# ExtConn.net
KiCad netlist of a schematic drawn in Altium Designer
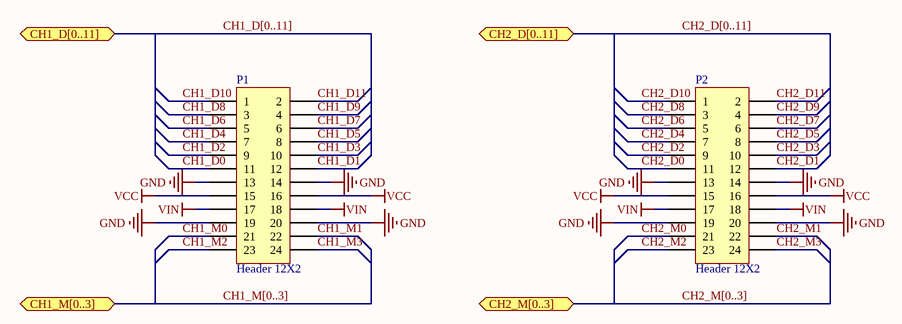
[diagram p0: ExtConn.SchDoc]

(export (version "E")
  (design (tool "Eeschema 10.0.6"))
  (components
    (comp (ref "P1")
      (value "Header 12X2")
      (footprint "HDR2X12")
      (description "Header, 12-Pin, Dual row")
      (fields (field (name "PUBLISHER") "Altium Limited"))
      (libsource (lib "Miscellaneous Connectors") (part "Header 12X2"))
    )
    (comp (ref "P2")
      (value "Header 12X2")
      (footprint "HDR2X12")
      (description "Header, 12-Pin, Dual row")
      (fields (field (name "PUBLISHER") "Altium Limited"))
      (libsource (lib "Miscellaneous Connectors") (part "Header 12X2"))
    )
  )
  (nets
    (net (code "1") (name "/CH1_D0") (class "Default")
      (node (ref "P1") (pin "11") (pinfunction "11_11") (pintype "passive"))
    )
    (net (code "2") (name "/CH1_D1") (class "Default")
      (node (ref "P1") (pin "12") (pinfunction "12_12") (pintype "passive"))
    )
    (net (code "3") (name "/CH1_D2") (class "Default")
      (node (ref "P1") (pin "9") (pinfunction "9_9") (pintype "passive"))
    )
    (net (code "4") (name "/CH1_D3") (class "Default")
      (node (ref "P1") (pin "10") (pinfunction "10_10") (pintype "passive"))
    )
    (net (code "5") (name "/CH1_D4") (class "Default")
      (node (ref "P1") (pin "7") (pinfunction "7_7") (pintype "passive"))
    )
    (net (code "6") (name "/CH1_D5") (class "Default")
      (node (ref "P1") (pin "8") (pinfunction "8_8") (pintype "passive"))
    )
    (net (code "7") (name "/CH1_D6") (class "Default")
      (node (ref "P1") (pin "5") (pinfunction "5_5") (pintype "passive"))
    )
    (net (code "8") (name "/CH1_D7") (class "Default")
      (node (ref "P1") (pin "6") (pinfunction "6_6") (pintype "passive"))
    )
    (net (code "9") (name "/CH1_D8") (class "Default")
      (node (ref "P1") (pin "3") (pinfunction "3_3") (pintype "passive"))
    )
    (net (code "10") (name "/CH1_D9") (class "Default")
      (node (ref "P1") (pin "4") (pinfunction "4_4") (pintype "passive"))
    )
    (net (code "11") (name "/CH1_D10") (class "Default")
      (node (ref "P1") (pin "1") (pinfunction "1_1") (pintype "passive"))
    )
    (net (code "12") (name "/CH1_D11") (class "Default")
      (node (ref "P1") (pin "2") (pinfunction "2_2") (pintype "passive"))
    )
    (net (code "14") (name "/CH1_M0") (class "Default")
      (node (ref "P1") (pin "21") (pinfunction "21_21") (pintype "passive"))
    )
    (net (code "15") (name "/CH1_M1") (class "Default")
      (node (ref "P1") (pin "22") (pinfunction "22_22") (pintype "passive"))
    )
    (net (code "16") (name "/CH1_M2") (class "Default")
      (node (ref "P1") (pin "23") (pinfunction "23_23") (pintype "passive"))
    )
    (net (code "17") (name "/CH1_M3") (class "Default")
      (node (ref "P1") (pin "24") (pinfunction "24_24") (pintype "passive"))
    )
    (net (code "19") (name "/CH2_D0") (class "Default")
      (node (ref "P2") (pin "11") (pinfunction "11_11") (pintype "passive"))
    )
    (net (code "20") (name "/CH2_D1") (class "Default")
      (node (ref "P2") (pin "12") (pinfunction "12_12") (pintype "passive"))
    )
    (net (code "21") (name "/CH2_D2") (class "Default")
      (node (ref "P2") (pin "9") (pinfunction "9_9") (pintype "passive"))
    )
    (net (code "22") (name "/CH2_D3") (class "Default")
      (node (ref "P2") (pin "10") (pinfunction "10_10") (pintype "passive"))
    )
    (net (code "23") (name "/CH2_D4") (class "Default")
      (node (ref "P2") (pin "7") (pinfunction "7_7") (pintype "passive"))
    )
    (net (code "24") (name "/CH2_D5") (class "Default")
      (node (ref "P2") (pin "8") (pinfunction "8_8") (pintype "passive"))
    )
    (net (code "25") (name "/CH2_D6") (class "Default")
      (node (ref "P2") (pin "5") (pinfunction "5_5") (pintype "passive"))
    )
    (net (code "26") (name "/CH2_D7") (class "Default")
      (node (ref "P2") (pin "6") (pinfunction "6_6") (pintype "passive"))
    )
    (net (code "27") (name "/CH2_D8") (class "Default")
      (node (ref "P2") (pin "3") (pinfunction "3_3") (pintype "passive"))
    )
    (net (code "28") (name "/CH2_D9") (class "Default")
      (node (ref "P2") (pin "4") (pinfunction "4_4") (pintype "passive"))
    )
    (net (code "29") (name "/CH2_D10") (class "Default")
      (node (ref "P2") (pin "1") (pinfunction "1_1") (pintype "passive"))
    )
    (net (code "30") (name "/CH2_D11") (class "Default")
      (node (ref "P2") (pin "2") (pinfunction "2_2") (pintype "passive"))
    )
    (net (code "32") (name "/CH2_M0") (class "Default")
      (node (ref "P2") (pin "21") (pinfunction "21_21") (pintype "passive"))
    )
    (net (code "33") (name "/CH2_M1") (class "Default")
      (node (ref "P2") (pin "22") (pinfunction "22_22") (pintype "passive"))
    )
    (net (code "34") (name "/CH2_M2") (class "Default")
      (node (ref "P2") (pin "23") (pinfunction "23_23") (pintype "passive"))
    )
    (net (code "35") (name "/CH2_M3") (class "Default")
      (node (ref "P2") (pin "24") (pinfunction "24_24") (pintype "passive"))
    )
    (net (code "37") (name "GND") (class "Default")
      (node (ref "P1") (pin "13") (pinfunction "13_13") (pintype "passive"))
      (node (ref "P1") (pin "14") (pinfunction "14_14") (pintype "passive"))
      (node (ref "P1") (pin "19") (pinfunction "19_19") (pintype "passive"))
      (node (ref "P1") (pin "20") (pinfunction "20_20") (pintype "passive"))
      (node (ref "P2") (pin "13") (pinfunction "13_13") (pintype "passive"))
      (node (ref "P2") (pin "14") (pinfunction "14_14") (pintype "passive"))
      (node (ref "P2") (pin "19") (pinfunction "19_19") (pintype "passive"))
      (node (ref "P2") (pin "20") (pinfunction "20_20") (pintype "passive"))
    )
    (net (code "38") (name "VCC") (class "Default")
      (node (ref "P1") (pin "15") (pinfunction "15_15") (pintype "passive"))
      (node (ref "P1") (pin "16") (pinfunction "16_16") (pintype "passive"))
      (node (ref "P2") (pin "15") (pinfunction "15_15") (pintype "passive"))
      (node (ref "P2") (pin "16") (pinfunction "16_16") (pintype "passive"))
    )
    (net (code "39") (name "VIN") (class "Default")
      (node (ref "P1") (pin "17") (pinfunction "17_17") (pintype "passive"))
      (node (ref "P1") (pin "18") (pinfunction "18_18") (pintype "passive"))
      (node (ref "P2") (pin "17") (pinfunction "17_17") (pintype "passive"))
      (node (ref "P2") (pin "18") (pinfunction "18_18") (pintype "passive"))
    )
  )
)
